# Wifi_Cellular_MD_and_FRAM.net
KiCad netlist of a schematic drawn in Altium Designer
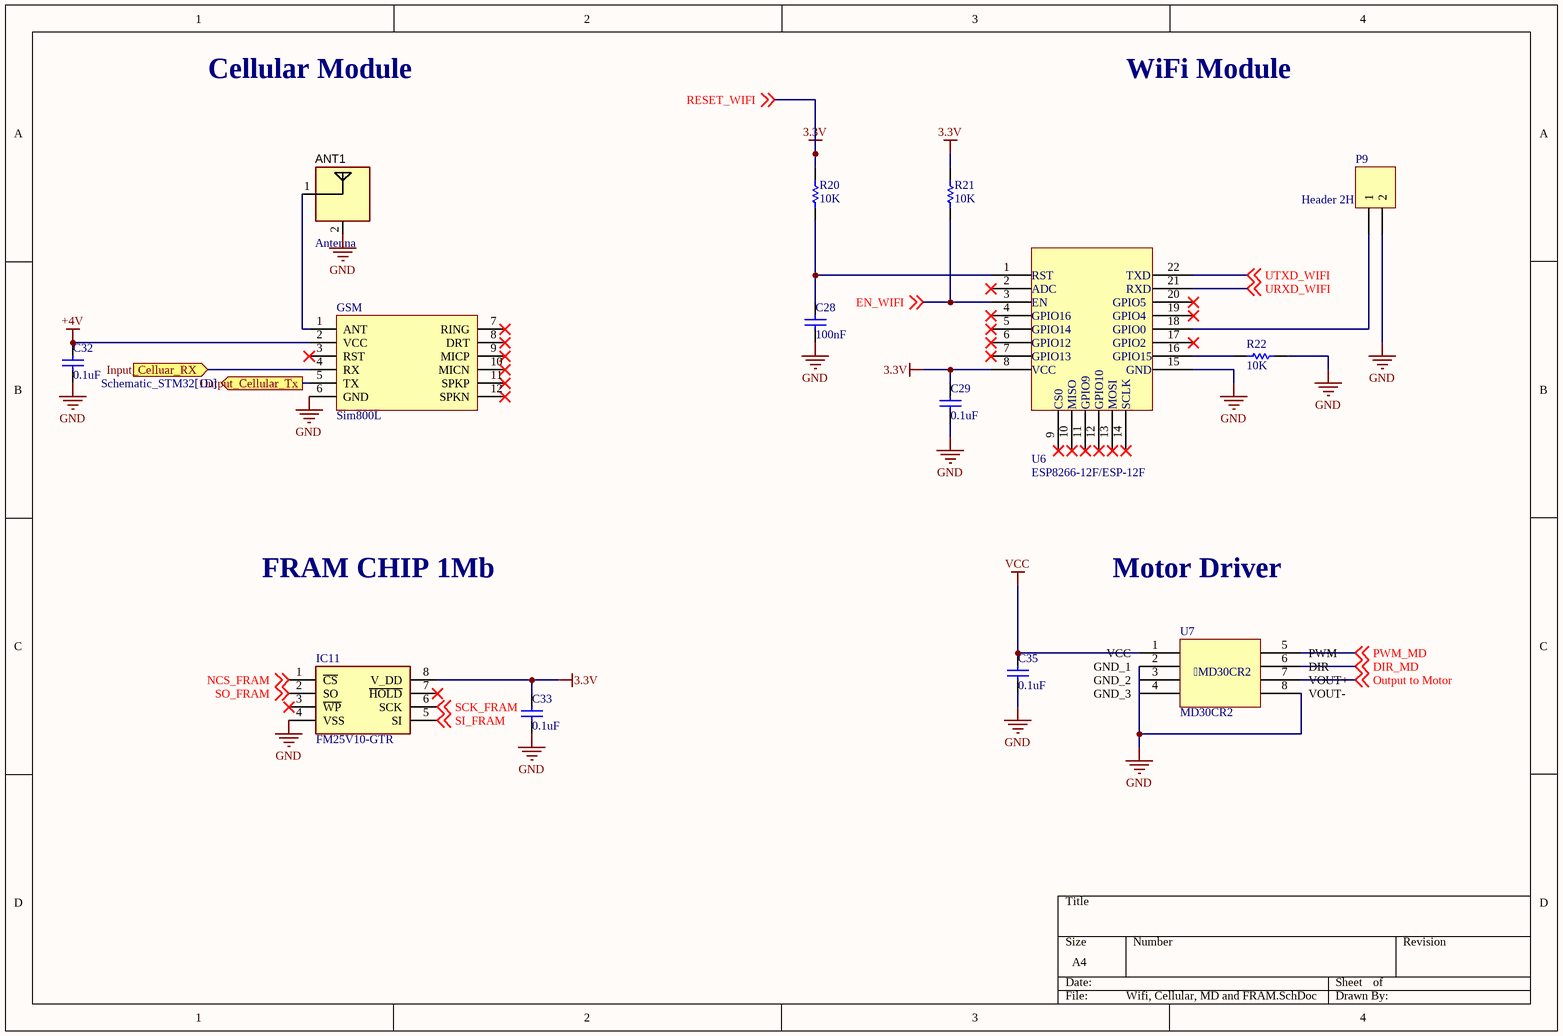
[diagram p0: Wifi, Cellular, MD and FRAM.SchDoc]

(export (version "E")
  (design (tool "Eeschema 10.0.6"))
  (components
    (comp (ref "ANT1")
      (value "Antenna")
      (footprint "ANT_IFA_2P4G")
      (description "TEST POINT")
      (fields (field (name "MANF") "MANF") (field (name "MANF_P#") "MANF_P#"))
      (libsource (lib "antenna") (part "TESTPOINT_SMD"))
    )
    (comp (ref "C28")
      (value "100nF")
      (footprint "RAD-0.3")
      (description "Capacitor")
      (fields (field (name "Comment") "Cap") (field (name "PUBLISHER") "Altium Limited"))
      (libsource (lib "Miscellaneous Devices") (part "Cap"))
    )
    (comp (ref "C29")
      (value "0.1uF")
      (footprint "RAD-0.3")
      (description "Capacitor")
      (fields (field (name "Comment") "Cap") (field (name "PUBLISHER") "Altium Limited"))
      (libsource (lib "Miscellaneous Devices") (part "Cap"))
    )
    (comp (ref "C32")
      (value "0.1uF")
      (footprint "RAD-0.3")
      (description "Capacitor")
      (fields (field (name "Comment") "Cap") (field (name "PUBLISHER") "Altium Limited"))
      (libsource (lib "Miscellaneous Devices") (part "Cap"))
    )
    (comp (ref "C33")
      (value "0.1uF")
      (footprint "RAD-0.3")
      (description "Capacitor")
      (fields (field (name "Comment") "Cap") (field (name "PUBLISHER") "Altium Limited"))
      (libsource (lib "Miscellaneous Devices") (part "Cap"))
    )
    (comp (ref "C35")
      (value "0.1uF")
      (footprint "RAD-0.3")
      (description "Capacitor")
      (fields (field (name "Comment") "Cap") (field (name "PUBLISHER") "Altium Limited"))
      (libsource (lib "Miscellaneous Devices") (part "Cap"))
    )
    (comp (ref "GSM")
      (value "Sim800L")
      (footprint "Sim800L")
      (description "GSM SIM800L")
      (libsource (lib "Sim800L_Module") (part "Sim800L"))
    )
    (comp (ref "IC11")
      (value "FM25V10-GTR")
      (footprint "SamacSys:SOIC127P602X173-8N")
      (description "Integrated Circuit")
      (fields (field (name "MOUSER PART NUMBER") "877-FM25V10-GTR"))
      (libsource (lib "*") (part "FM25V10-GTR"))
    )
    (comp (ref "P9")
      (value "Header 2H")
      (footprint "HDR1X2H")
      (description "Header, 2-Pin, Right Angle")
      (fields (field (name "PUBLISHER") "Altium Limited"))
      (libsource (lib "Miscellaneous Connectors") (part "Header 2H"))
    )
    (comp (ref "R20")
      (value "10K")
      (footprint "AXIAL-0.3")
      (description "Resistor")
      (fields (field (name "Comment") "Res1") (field (name "PUBLISHER") "Altium Limited"))
      (libsource (lib "Miscellaneous Devices") (part "Res1"))
    )
    (comp (ref "R21")
      (value "10K")
      (footprint "AXIAL-0.3")
      (description "Resistor")
      (fields (field (name "Comment") "Res1") (field (name "PUBLISHER") "Altium Limited"))
      (libsource (lib "Miscellaneous Devices") (part "Res1"))
    )
    (comp (ref "R22")
      (value "10K")
      (footprint "AXIAL-0.3")
      (description "Resistor")
      (fields (field (name "Comment") "Res1") (field (name "PUBLISHER") "Altium Limited"))
      (libsource (lib "Miscellaneous Devices") (part "Res1"))
    )
    (comp (ref "U6")
      (value "ESP8266-12F/ESP-12F")
      (description "Integrated Circuit")
      (libsource (lib "WIFI") (part "ESP-12F"))
    )
    (comp (ref "U7")
      (value "MD30CR2")
      (description "Motor Driver")
      (libsource (lib "MD30CR2") (part "MD30CR2"))
    )
  )
  (nets
    (net (code "1") (name "+4V") (class "Default")
      (node (ref "C32") (pin "2") (pinfunction "2_2") (pintype "passive"))
      (node (ref "GSM") (pin "2") (pinfunction "VCC_2") (pintype "passive"))
    )
    (net (code "2") (name "/Input_Celluar_RX") (class "Default")
      (node (ref "GSM") (pin "4") (pinfunction "RX_4") (pintype "passive"))
    )
    (net (code "3") (name "/Output_Cellular_Tx") (class "Default")
      (node (ref "GSM") (pin "5") (pinfunction "TX_5") (pintype "passive"))
    )
    (net (code "4") (name "3.3V") (class "Default")
      (node (ref "C29") (pin "2") (pinfunction "2_2") (pintype "passive"))
      (node (ref "C33") (pin "2") (pinfunction "2_2") (pintype "passive"))
      (node (ref "IC11") (pin "8") (pinfunction "V_DD_8") (pintype "passive"))
      (node (ref "R20") (pin "1") (pinfunction "1_1") (pintype "passive"))
      (node (ref "R21") (pin "1") (pinfunction "1_1") (pintype "passive"))
    )
    (net (code "6") (name "EN_WIFI") (class "Default")
      (node (ref "R21") (pin "2") (pinfunction "2_2") (pintype "passive"))
    )
    (net (code "7") (name "GND") (class "Default")
      (node (ref "ANT1") (pin "2") (pinfunction "GND_2") (pintype "passive"))
      (node (ref "C28") (pin "1") (pinfunction "1_1") (pintype "passive"))
      (node (ref "C29") (pin "1") (pinfunction "1_1") (pintype "passive"))
      (node (ref "C32") (pin "1") (pinfunction "1_1") (pintype "passive"))
      (node (ref "C33") (pin "1") (pinfunction "1_1") (pintype "passive"))
      (node (ref "C35") (pin "1") (pinfunction "1_1") (pintype "passive"))
      (node (ref "GSM") (pin "6") (pinfunction "GND_6") (pintype "passive"))
      (node (ref "IC11") (pin "4") (pinfunction "VSS_4") (pintype "passive"))
      (node (ref "P9") (pin "2") (pinfunction "2_2") (pintype "passive"))
      (node (ref "R22") (pin "2") (pinfunction "2_2") (pintype "passive"))
    )
    (net (code "8") (name "NCS_FRAM") (class "Default")
      (node (ref "IC11") (pin "1") (pinfunction "~{CS}_1") (pintype "passive"))
    )
    (net (code "9") (name "Net-(C28-Pad2)") (class "Default")
      (node (ref "C28") (pin "2") (pinfunction "2_2") (pintype "passive"))
      (node (ref "R20") (pin "2") (pinfunction "2_2") (pintype "passive"))
    )
    (net (code "10") (name "Net-(GSM-ANT)") (class "Default")
      (node (ref "ANT1") (pin "1") (pinfunction "1_1") (pintype "passive"))
      (node (ref "GSM") (pin "1") (pinfunction "ANT_1") (pintype "passive"))
    )
    (net (code "13") (name "SCK_FRAM") (class "Default")
      (node (ref "IC11") (pin "6") (pinfunction "SCK_6") (pintype "passive"))
    )
    (net (code "14") (name "SI_FRAM") (class "Default")
      (node (ref "IC11") (pin "5") (pinfunction "SI_5") (pintype "passive"))
    )
    (net (code "15") (name "SO_FRAM") (class "Default")
      (node (ref "IC11") (pin "2") (pinfunction "SO_2") (pintype "passive"))
    )
    (net (code "18") (name "VCC") (class "Default")
      (node (ref "C35") (pin "2") (pinfunction "2_2") (pintype "passive"))
    )
    (net (code "19") (name "unconnected-(GSM-DRT-Pad8)") (class "Default")
      (node (ref "GSM") (pin "8") (pinfunction "DRT_8") (pintype "passive+no_connect"))
    )
    (net (code "20") (name "unconnected-(GSM-MICN-Pad10)") (class "Default")
      (node (ref "GSM") (pin "10") (pinfunction "MICN_10") (pintype "passive+no_connect"))
    )
    (net (code "21") (name "unconnected-(GSM-MICP-Pad9)") (class "Default")
      (node (ref "GSM") (pin "9") (pinfunction "MICP_9") (pintype "passive+no_connect"))
    )
    (net (code "22") (name "unconnected-(GSM-RING-Pad7)") (class "Default")
      (node (ref "GSM") (pin "7") (pinfunction "RING_7") (pintype "passive+no_connect"))
    )
    (net (code "23") (name "unconnected-(GSM-RST-Pad3)") (class "Default")
      (node (ref "GSM") (pin "3") (pinfunction "RST_3") (pintype "passive+no_connect"))
    )
    (net (code "24") (name "unconnected-(GSM-SPKN-Pad12)") (class "Default")
      (node (ref "GSM") (pin "12") (pinfunction "SPKN_12") (pintype "passive+no_connect"))
    )
    (net (code "25") (name "unconnected-(GSM-SPKP-Pad11)") (class "Default")
      (node (ref "GSM") (pin "11") (pinfunction "SPKP_11") (pintype "passive+no_connect"))
    )
    (net (code "26") (name "unconnected-(IC11-~{HOLD}-Pad7)") (class "Default")
      (node (ref "IC11") (pin "7") (pinfunction "~{HOLD}_7") (pintype "passive+no_connect"))
    )
    (net (code "27") (name "unconnected-(IC11-~{WP}-Pad3)") (class "Default")
      (node (ref "IC11") (pin "3") (pinfunction "~{WP}_3") (pintype "passive+no_connect"))
    )
    (net (code "28") (name "unconnected-(P9-Pad1)") (class "Default")
      (node (ref "P9") (pin "1") (pinfunction "1_1") (pintype "passive"))
    )
    (net (code "29") (name "unconnected-(R22-Pad1)") (class "Default")
      (node (ref "R22") (pin "1") (pinfunction "1_1") (pintype "passive"))
    )
    (net (code "30") (name "unconnected-(U6-8-Pad11)") (class "Default")
      (node (ref "U6") (pin "11") (pinfunction "8_11") (pintype "passive"))
    )
    (net (code "31") (name "unconnected-(U6-8-Pad12)") (class "Default")
      (node (ref "U6") (pin "12") (pinfunction "8_12") (pintype "passive"))
    )
    (net (code "32") (name "unconnected-(U6-8-Pad13)") (class "Default")
      (node (ref "U6") (pin "13") (pinfunction "8_13") (pintype "passive"))
    )
    (net (code "33") (name "unconnected-(U6-8-Pad14)") (class "Default")
      (node (ref "U6") (pin "14") (pinfunction "8_14") (pintype "passive"))
    )
    (net (code "34") (name "unconnected-(U6-ADC-Pad2)") (class "Default")
      (node (ref "U6") (pin "2") (pinfunction "ADC_2") (pintype "passive"))
    )
    (net (code "35") (name "unconnected-(U6-CS0-Pad9)") (class "Default")
      (node (ref "U6") (pin "9") (pinfunction "CS0_9") (pintype "passive"))
    )
    (net (code "36") (name "unconnected-(U6-EN-Pad3)") (class "Default")
      (node (ref "U6") (pin "3") (pinfunction "EN_3") (pintype "passive"))
    )
    (net (code "37") (name "unconnected-(U6-GND-Pad15)") (class "Default")
      (node (ref "U6") (pin "15") (pinfunction "GND_15") (pintype "passive"))
    )
    (net (code "38") (name "unconnected-(U6-GPIO0-Pad18)") (class "Default")
      (node (ref "U6") (pin "18") (pinfunction "GPIO0_18") (pintype "passive"))
    )
    (net (code "39") (name "unconnected-(U6-GPIO2-Pad17)") (class "Default")
      (node (ref "U6") (pin "17") (pinfunction "GPIO2_17") (pintype "passive"))
    )
    (net (code "40") (name "unconnected-(U6-GPIO4-Pad19)") (class "Default")
      (node (ref "U6") (pin "19") (pinfunction "GPIO4_19") (pintype "passive"))
    )
    (net (code "41") (name "unconnected-(U6-GPIO5-Pad20)") (class "Default")
      (node (ref "U6") (pin "20") (pinfunction "GPIO5_20") (pintype "passive"))
    )
    (net (code "42") (name "unconnected-(U6-GPIO12-Pad6)") (class "Default")
      (node (ref "U6") (pin "6") (pinfunction "GPIO12_6") (pintype "passive"))
    )
    (net (code "43") (name "unconnected-(U6-GPIO13-Pad7)") (class "Default")
      (node (ref "U6") (pin "7") (pinfunction "GPIO13_7") (pintype "passive"))
    )
    (net (code "44") (name "unconnected-(U6-GPIO14-Pad5)") (class "Default")
      (node (ref "U6") (pin "5") (pinfunction "GPIO14_5") (pintype "passive"))
    )
    (net (code "45") (name "unconnected-(U6-GPIO15-Pad16)") (class "Default")
      (node (ref "U6") (pin "16") (pinfunction "GPIO15_16") (pintype "passive"))
    )
    (net (code "46") (name "unconnected-(U6-GPIO16-Pad4)") (class "Default")
      (node (ref "U6") (pin "4") (pinfunction "GPIO16_4") (pintype "passive"))
    )
    (net (code "47") (name "unconnected-(U6-MISO-Pad10)") (class "Default")
      (node (ref "U6") (pin "10") (pinfunction "MISO_10") (pintype "passive"))
    )
    (net (code "48") (name "unconnected-(U6-RST-Pad1)") (class "Default")
      (node (ref "U6") (pin "1") (pinfunction "RST_1") (pintype "passive"))
    )
    (net (code "49") (name "unconnected-(U6-RXD-Pad21)") (class "Default")
      (node (ref "U6") (pin "21") (pinfunction "RXD_21") (pintype "passive"))
    )
    (net (code "50") (name "unconnected-(U6-TXD-Pad22)") (class "Default")
      (node (ref "U6") (pin "22") (pinfunction "TXD_22") (pintype "passive"))
    )
    (net (code "51") (name "unconnected-(U6-VCC-Pad8)") (class "Default")
      (node (ref "U6") (pin "8") (pinfunction "VCC_8") (pintype "passive"))
    )
    (net (code "52") (name "unconnected-(U7-DIR-Pad6)") (class "Default")
      (node (ref "U7") (pin "6") (pinfunction "DIR_6") (pintype "passive"))
    )
    (net (code "53") (name "unconnected-(U7-GND_1-Pad2)") (class "Default")
      (node (ref "U7") (pin "2") (pinfunction "GND_1_2") (pintype "power_in"))
    )
    (net (code "54") (name "unconnected-(U7-GND_2-Pad3)") (class "Default")
      (node (ref "U7") (pin "3") (pinfunction "GND_2_3") (pintype "power_in"))
    )
    (net (code "55") (name "unconnected-(U7-GND_3-Pad4)") (class "Default")
      (node (ref "U7") (pin "4") (pinfunction "GND_3_4") (pintype "power_in"))
    )
    (net (code "56") (name "unconnected-(U7-PWM-Pad5)") (class "Default")
      (node (ref "U7") (pin "5") (pinfunction "PWM_5") (pintype "passive"))
    )
    (net (code "57") (name "unconnected-(U7-VCC-Pad1)") (class "Default")
      (node (ref "U7") (pin "1") (pinfunction "VCC_1") (pintype "power_in"))
    )
    (net (code "58") (name "unconnected-(U7-VOUT+-Pad7)") (class "Default")
      (node (ref "U7") (pin "7") (pinfunction "VOUT+_7") (pintype "passive"))
    )
    (net (code "59") (name "unconnected-(U7-VOUT--Pad8)") (class "Default")
      (node (ref "U7") (pin "8") (pinfunction "VOUT-_8") (pintype "passive"))
    )
  )
)
